# dali_adapter.net
KiCad netlist of a schematic drawn in EAGLE
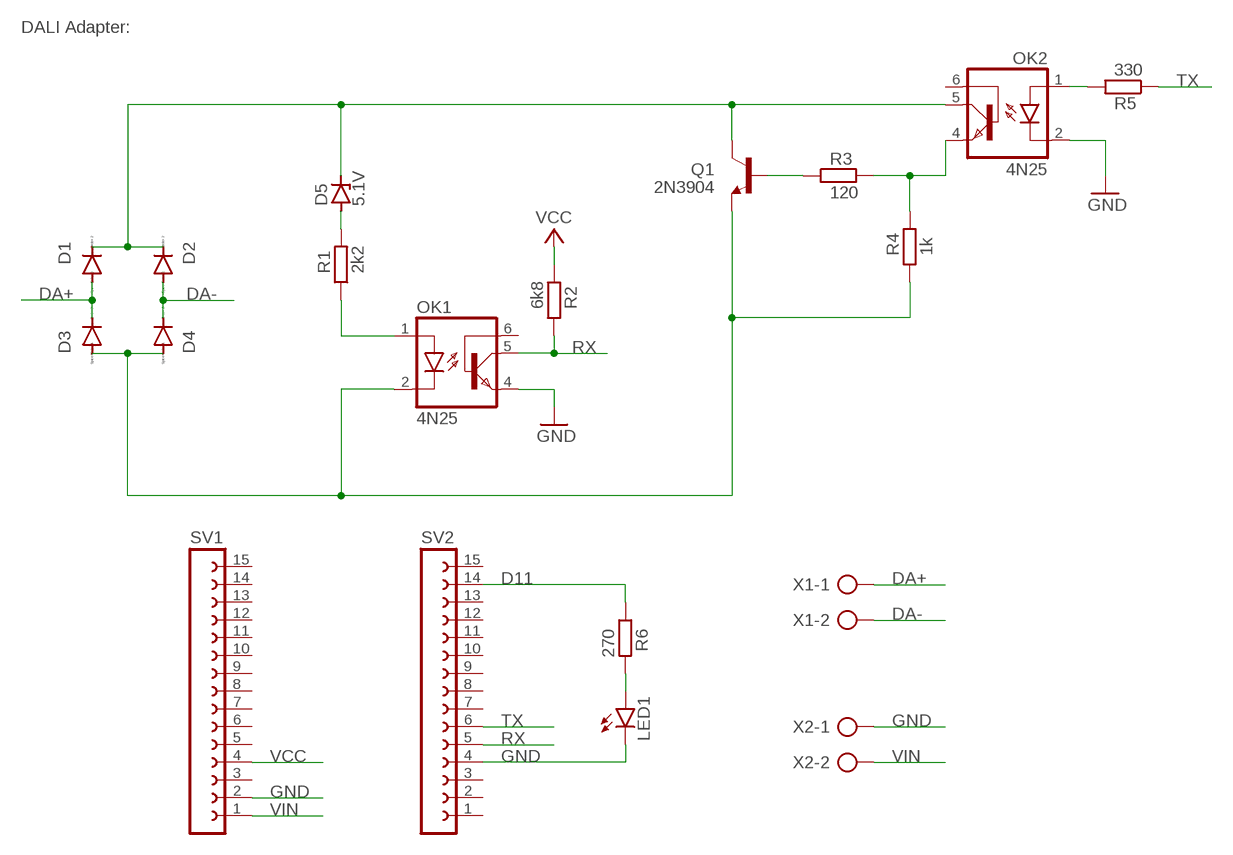
[diagram p0: schematic, sheet 1]

(export (version "E")
  (design (tool "Eeschema 10.0.6"))
  (components
    (comp (ref "D1")
      (value "1N4004")
      (footprint "eagle-import:DO41-10")
      (libsource (lib "eagle-import") (part "1N4004"))
    )
    (comp (ref "D2")
      (value "1N4004")
      (footprint "eagle-import:DO41-10")
      (libsource (lib "eagle-import") (part "1N4004"))
    )
    (comp (ref "D3")
      (value "1N4004")
      (footprint "eagle-import:DO41-10")
      (libsource (lib "eagle-import") (part "1N4004"))
    )
    (comp (ref "D4")
      (value "1N4004")
      (footprint "eagle-import:DO41-10")
      (libsource (lib "eagle-import") (part "1N4004"))
    )
    (comp (ref "D5")
      (value "5.1V")
      (footprint "eagle-import:DO35Z10")
      (libsource (lib "eagle-import") (part "ZENER-DIODEDO35Z10"))
    )
    (comp (ref "LED1")
      (value "LED5MM")
      (footprint "eagle-import:LED5MM")
      (libsource (lib "eagle-import") (part "LED5MM"))
    )
    (comp (ref "OK1")
      (value "4N25")
      (footprint "eagle-import:DIL06")
      (fields (field (name "MPN") "4N25-M"))
      (libsource (lib "eagle-import") (part "4N?M25"))
    )
    (comp (ref "OK2")
      (value "4N25")
      (footprint "eagle-import:DIL06")
      (fields (field (name "MPN") "4N25-M"))
      (libsource (lib "eagle-import") (part "4N?M25"))
    )
    (comp (ref "Q1")
      (value "2N3904")
      (footprint "eagle-import:TO92-EBC")
      (libsource (lib "eagle-import") (part "BC449"))
    )
    (comp (ref "R1")
      (value "2k2")
      (footprint "eagle-import:0207_10")
      (libsource (lib "eagle-import") (part "R-EU_0207/10"))
    )
    (comp (ref "R2")
      (value "6k8")
      (footprint "eagle-import:0207_10")
      (libsource (lib "eagle-import") (part "R-EU_0207/10"))
    )
    (comp (ref "R3")
      (value "120")
      (footprint "eagle-import:0207_10")
      (libsource (lib "eagle-import") (part "R-EU_0207/10"))
    )
    (comp (ref "R4")
      (value "1k")
      (footprint "eagle-import:0207_10")
      (libsource (lib "eagle-import") (part "R-EU_0207/10"))
    )
    (comp (ref "R5")
      (value "330")
      (footprint "eagle-import:0207_10")
      (libsource (lib "eagle-import") (part "R-EU_0207/10"))
    )
    (comp (ref "R6")
      (value "270")
      (footprint "eagle-import:0207_10")
      (libsource (lib "eagle-import") (part "R-EU_0207/10"))
    )
    (comp (ref "SV1")
      (value "FE15-1")
      (footprint "eagle-import:FE15")
      (libsource (lib "eagle-import") (part "FE15-1"))
    )
    (comp (ref "SV2")
      (value "FE15-1")
      (footprint "eagle-import:FE15")
      (libsource (lib "eagle-import") (part "FE15-1"))
    )
    (comp (ref "X1")
      (value "AK500/2")
      (footprint "eagle-import:AK500_2")
      (libsource (lib "eagle-import") (part "AK500/2"))
    )
    (comp (ref "X2")
      (value "AK500/2")
      (footprint "eagle-import:AK500_2")
      (libsource (lib "eagle-import") (part "AK500/2"))
    )
  )
  (nets
    (net (code "1") (name "/D11") (class "Default")
      (node (ref "R6") (pin "1") (pinfunction "1_1") (pintype "passive"))
      (node (ref "SV2") (pin "14") (pinfunction "14_14") (pintype "passive"))
    )
    (net (code "2") (name "/DA+") (class "Default")
      (node (ref "D1") (pin "A") (pinfunction "A_A") (pintype "passive"))
      (node (ref "D3") (pin "C") (pinfunction "C_C") (pintype "passive"))
      (node (ref "X1") (pin "1") (pinfunction "KL_1") (pintype "passive"))
    )
    (net (code "3") (name "/DA-") (class "Default")
      (node (ref "D2") (pin "A") (pinfunction "A_A") (pintype "passive"))
      (node (ref "D4") (pin "C") (pinfunction "C_C") (pintype "passive"))
      (node (ref "X1") (pin "2") (pinfunction "KL_2") (pintype "passive"))
    )
    (net (code "4") (name "/RX") (class "Default")
      (node (ref "OK1") (pin "5") (pinfunction "COL_5") (pintype "passive"))
      (node (ref "R2") (pin "2") (pinfunction "2_2") (pintype "passive"))
      (node (ref "SV2") (pin "5") (pinfunction "5_5") (pintype "passive"))
    )
    (net (code "5") (name "/TX") (class "Default")
      (node (ref "R5") (pin "1") (pinfunction "1_1") (pintype "passive"))
      (node (ref "SV2") (pin "6") (pinfunction "6_6") (pintype "passive"))
    )
    (net (code "6") (name "/VIN") (class "Default")
      (node (ref "SV1") (pin "1") (pinfunction "1_1") (pintype "passive"))
      (node (ref "X2") (pin "2") (pinfunction "KL_2") (pintype "passive"))
    )
    (net (code "7") (name "GND") (class "Default")
      (node (ref "LED1") (pin "K") (pinfunction "C_K") (pintype "passive"))
      (node (ref "OK1") (pin "4") (pinfunction "EMI_4") (pintype "passive"))
      (node (ref "OK2") (pin "2") (pinfunction "C_2") (pintype "passive"))
      (node (ref "SV1") (pin "2") (pinfunction "2_2") (pintype "passive"))
      (node (ref "SV2") (pin "4") (pinfunction "4_4") (pintype "passive"))
      (node (ref "X2") (pin "1") (pinfunction "KL_1") (pintype "passive"))
    )
    (net (code "8") (name "Net-(D5-PadA)") (class "Default")
      (node (ref "D5") (pin "A") (pinfunction "A_A") (pintype "passive"))
      (node (ref "R1") (pin "2") (pinfunction "2_2") (pintype "passive"))
    )
    (net (code "9") (name "Net-(LED1-PadA)") (class "Default")
      (node (ref "LED1") (pin "A") (pinfunction "A_A") (pintype "passive"))
      (node (ref "R6") (pin "2") (pinfunction "2_2") (pintype "passive"))
    )
    (net (code "10") (name "Net-(OK1-A)") (class "Default")
      (node (ref "OK1") (pin "1") (pinfunction "A_1") (pintype "passive"))
      (node (ref "R1") (pin "1") (pinfunction "1_1") (pintype "passive"))
    )
    (net (code "11") (name "Net-(OK1-C)") (class "Default")
      (node (ref "D3") (pin "A") (pinfunction "A_A") (pintype "passive"))
      (node (ref "D4") (pin "A") (pinfunction "A_A") (pintype "passive"))
      (node (ref "OK1") (pin "2") (pinfunction "C_2") (pintype "passive"))
      (node (ref "Q1") (pin "E") (pinfunction "E_E") (pintype "passive"))
      (node (ref "R4") (pin "1") (pinfunction "1_1") (pintype "passive"))
    )
    (net (code "12") (name "Net-(OK2-A)") (class "Default")
      (node (ref "OK2") (pin "1") (pinfunction "A_1") (pintype "passive"))
      (node (ref "R5") (pin "2") (pinfunction "2_2") (pintype "passive"))
    )
    (net (code "13") (name "Net-(OK2-COL)") (class "Default")
      (node (ref "D1") (pin "C") (pinfunction "C_C") (pintype "passive"))
      (node (ref "D2") (pin "C") (pinfunction "C_C") (pintype "passive"))
      (node (ref "D5") (pin "C") (pinfunction "C_C") (pintype "passive"))
      (node (ref "OK2") (pin "5") (pinfunction "COL_5") (pintype "passive"))
      (node (ref "Q1") (pin "C") (pinfunction "C_C") (pintype "passive"))
    )
    (net (code "14") (name "Net-(OK2-EMI)") (class "Default")
      (node (ref "OK2") (pin "4") (pinfunction "EMI_4") (pintype "passive"))
      (node (ref "R3") (pin "2") (pinfunction "2_2") (pintype "passive"))
      (node (ref "R4") (pin "2") (pinfunction "2_2") (pintype "passive"))
    )
    (net (code "15") (name "Net-(Q1-PadB)") (class "Default")
      (node (ref "Q1") (pin "B") (pinfunction "B_B") (pintype "passive"))
      (node (ref "R3") (pin "1") (pinfunction "1_1") (pintype "passive"))
    )
    (net (code "16") (name "VCC") (class "Default")
      (node (ref "R2") (pin "1") (pinfunction "1_1") (pintype "passive"))
      (node (ref "SV1") (pin "4") (pinfunction "4_4") (pintype "passive"))
    )
    (net (code "17") (name "unconnected-(OK1-BAS-Pad6)") (class "Default")
      (node (ref "OK1") (pin "6") (pinfunction "BAS_6") (pintype "passive"))
    )
    (net (code "18") (name "unconnected-(OK2-BAS-Pad6)") (class "Default")
      (node (ref "OK2") (pin "6") (pinfunction "BAS_6") (pintype "passive"))
    )
    (net (code "19") (name "unconnected-(SV1-Pad3)") (class "Default")
      (node (ref "SV1") (pin "3") (pinfunction "3_3") (pintype "passive"))
    )
    (net (code "20") (name "unconnected-(SV1-Pad5)") (class "Default")
      (node (ref "SV1") (pin "5") (pinfunction "5_5") (pintype "passive"))
    )
    (net (code "21") (name "unconnected-(SV1-Pad6)") (class "Default")
      (node (ref "SV1") (pin "6") (pinfunction "6_6") (pintype "passive"))
    )
    (net (code "22") (name "unconnected-(SV1-Pad7)") (class "Default")
      (node (ref "SV1") (pin "7") (pinfunction "7_7") (pintype "passive"))
    )
    (net (code "23") (name "unconnected-(SV1-Pad8)") (class "Default")
      (node (ref "SV1") (pin "8") (pinfunction "8_8") (pintype "passive"))
    )
    (net (code "24") (name "unconnected-(SV1-Pad9)") (class "Default")
      (node (ref "SV1") (pin "9") (pinfunction "9_9") (pintype "passive"))
    )
    (net (code "25") (name "unconnected-(SV1-Pad10)") (class "Default")
      (node (ref "SV1") (pin "10") (pinfunction "10_10") (pintype "passive"))
    )
    (net (code "26") (name "unconnected-(SV1-Pad11)") (class "Default")
      (node (ref "SV1") (pin "11") (pinfunction "11_11") (pintype "passive"))
    )
    (net (code "27") (name "unconnected-(SV1-Pad12)") (class "Default")
      (node (ref "SV1") (pin "12") (pinfunction "12_12") (pintype "passive"))
    )
    (net (code "28") (name "unconnected-(SV1-Pad13)") (class "Default")
      (node (ref "SV1") (pin "13") (pinfunction "13_13") (pintype "passive"))
    )
    (net (code "29") (name "unconnected-(SV1-Pad14)") (class "Default")
      (node (ref "SV1") (pin "14") (pinfunction "14_14") (pintype "passive"))
    )
    (net (code "30") (name "unconnected-(SV1-Pad15)") (class "Default")
      (node (ref "SV1") (pin "15") (pinfunction "15_15") (pintype "passive"))
    )
    (net (code "31") (name "unconnected-(SV2-Pad1)") (class "Default")
      (node (ref "SV2") (pin "1") (pinfunction "1_1") (pintype "passive"))
    )
    (net (code "32") (name "unconnected-(SV2-Pad2)") (class "Default")
      (node (ref "SV2") (pin "2") (pinfunction "2_2") (pintype "passive"))
    )
    (net (code "33") (name "unconnected-(SV2-Pad3)") (class "Default")
      (node (ref "SV2") (pin "3") (pinfunction "3_3") (pintype "passive"))
    )
    (net (code "34") (name "unconnected-(SV2-Pad7)") (class "Default")
      (node (ref "SV2") (pin "7") (pinfunction "7_7") (pintype "passive"))
    )
    (net (code "35") (name "unconnected-(SV2-Pad8)") (class "Default")
      (node (ref "SV2") (pin "8") (pinfunction "8_8") (pintype "passive"))
    )
    (net (code "36") (name "unconnected-(SV2-Pad9)") (class "Default")
      (node (ref "SV2") (pin "9") (pinfunction "9_9") (pintype "passive"))
    )
    (net (code "37") (name "unconnected-(SV2-Pad10)") (class "Default")
      (node (ref "SV2") (pin "10") (pinfunction "10_10") (pintype "passive"))
    )
    (net (code "38") (name "unconnected-(SV2-Pad11)") (class "Default")
      (node (ref "SV2") (pin "11") (pinfunction "11_11") (pintype "passive"))
    )
    (net (code "39") (name "unconnected-(SV2-Pad12)") (class "Default")
      (node (ref "SV2") (pin "12") (pinfunction "12_12") (pintype "passive"))
    )
    (net (code "40") (name "unconnected-(SV2-Pad13)") (class "Default")
      (node (ref "SV2") (pin "13") (pinfunction "13_13") (pintype "passive"))
    )
    (net (code "41") (name "unconnected-(SV2-Pad15)") (class "Default")
      (node (ref "SV2") (pin "15") (pinfunction "15_15") (pintype "passive"))
    )
  )
)
